# OBC_EEPROM.net
KiCad netlist of a schematic drawn in Altium Designer
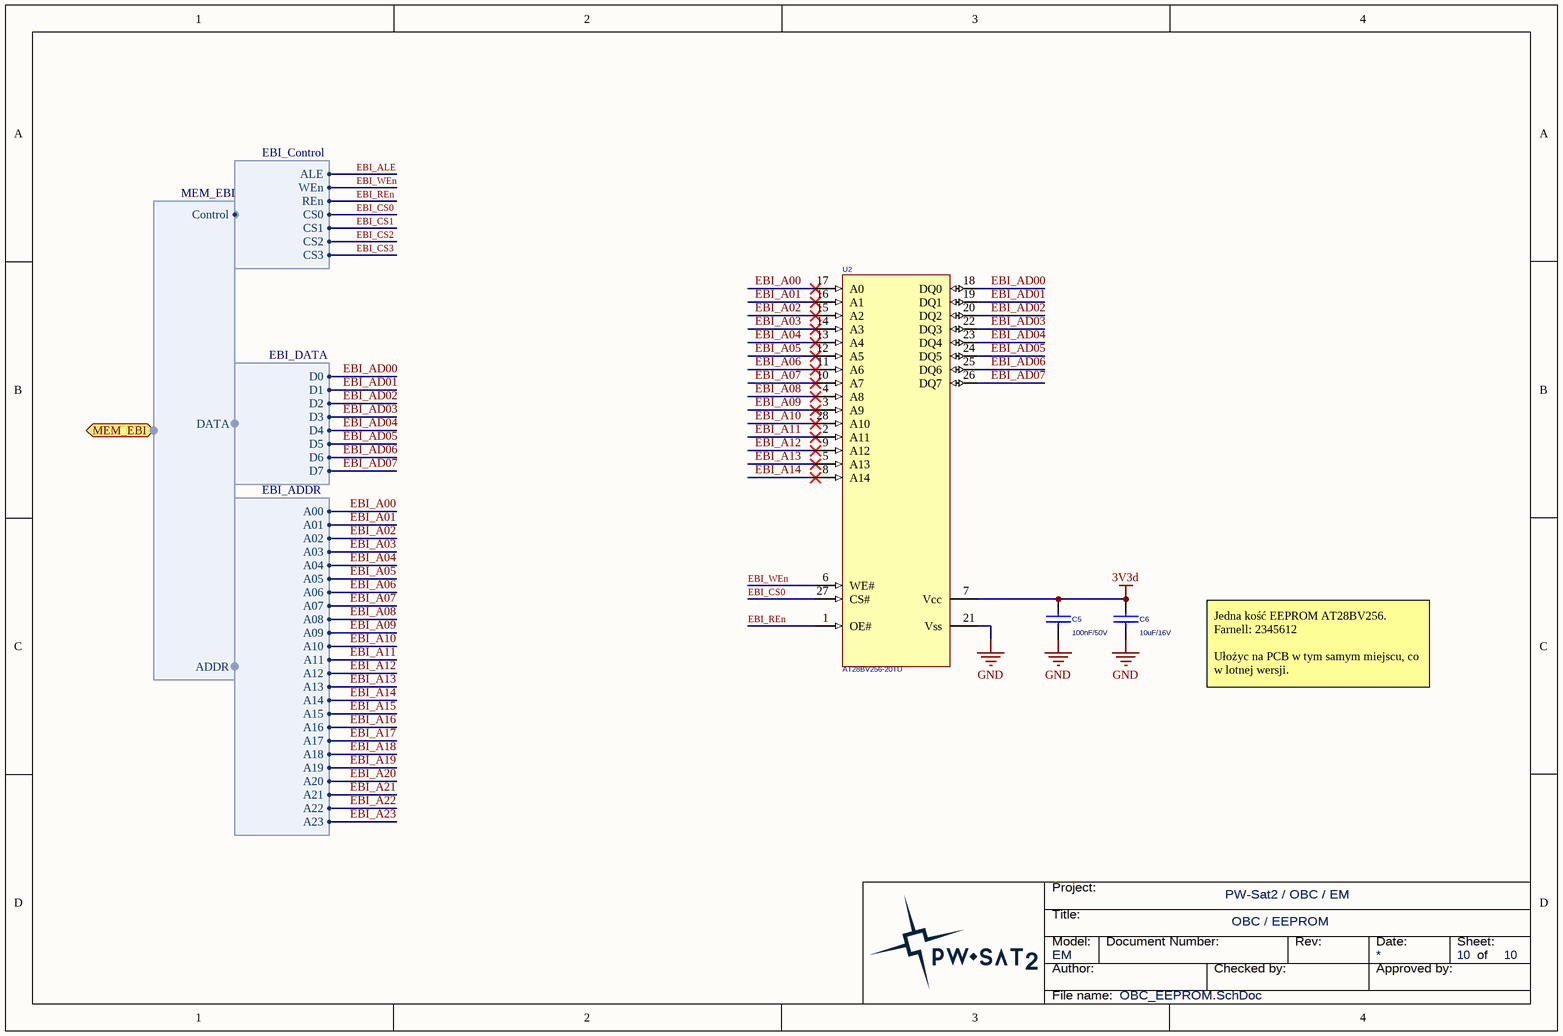
[diagram p0: OBC_EEPROM.SchDoc]

(export (version "E")
  (design (tool "Eeschema 10.0.6"))
  (components
    (comp (ref "C5")
      (value "100nF/50V")
      (footprint "C0603")
      (description "Capacitator")
      (fields (field (name "VOLTAGE") "50V"))
      (libsource (lib "SchLib") (part "CAP"))
    )
    (comp (ref "C6")
      (value "10uF/16V")
      (footprint "C1206")
      (description "Capacitator")
      (fields (field (name "VOLTAGE") "16V"))
      (libsource (lib "SchLib") (part "CAP"))
    )
    (comp (ref "U2")
      (value "AT28BV256-20TU")
      (footprint "TSOP-28T")
      (description "256K (32K x 8)  Battery-Voltage  Parallel  EEPROMs")
      (fields (field (name "MANUFACTURER") "Microchip Technology"))
      (libsource (lib "OBC") (part "AT28BV256-20TU"))
    )
  )
  (nets
    (net (code "2") (name "/EBI_A00") (class "Default")
      (node (ref "U2") (pin "17") (pinfunction "A0_17") (pintype "input"))
    )
    (net (code "3") (name "/EBI_A01") (class "Default")
      (node (ref "U2") (pin "16") (pinfunction "A1_16") (pintype "input"))
    )
    (net (code "4") (name "/EBI_A02") (class "Default")
      (node (ref "U2") (pin "15") (pinfunction "A2_15") (pintype "input"))
    )
    (net (code "5") (name "/EBI_A03") (class "Default")
      (node (ref "U2") (pin "14") (pinfunction "A3_14") (pintype "input"))
    )
    (net (code "6") (name "/EBI_A04") (class "Default")
      (node (ref "U2") (pin "13") (pinfunction "A4_13") (pintype "input"))
    )
    (net (code "7") (name "/EBI_A05") (class "Default")
      (node (ref "U2") (pin "12") (pinfunction "A5_12") (pintype "input+no_connect"))
    )
    (net (code "8") (name "/EBI_A06") (class "Default")
      (node (ref "U2") (pin "11") (pinfunction "A6_11") (pintype "input+no_connect"))
    )
    (net (code "9") (name "/EBI_A07") (class "Default")
      (node (ref "U2") (pin "10") (pinfunction "A7_10") (pintype "input+no_connect"))
    )
    (net (code "10") (name "/EBI_A08") (class "Default")
      (node (ref "U2") (pin "4") (pinfunction "A8_4") (pintype "input+no_connect"))
    )
    (net (code "11") (name "/EBI_A09") (class "Default")
      (node (ref "U2") (pin "3") (pinfunction "A9_3") (pintype "input+no_connect"))
    )
    (net (code "12") (name "/EBI_A10") (class "Default")
      (node (ref "U2") (pin "28") (pinfunction "A10_28") (pintype "input+no_connect"))
    )
    (net (code "13") (name "/EBI_A11") (class "Default")
      (node (ref "U2") (pin "2") (pinfunction "A11_2") (pintype "input+no_connect"))
    )
    (net (code "14") (name "/EBI_A12") (class "Default")
      (node (ref "U2") (pin "9") (pinfunction "A12_9") (pintype "input+no_connect"))
    )
    (net (code "15") (name "/EBI_A13") (class "Default")
      (node (ref "U2") (pin "5") (pinfunction "A13_5") (pintype "input+no_connect"))
    )
    (net (code "16") (name "/EBI_A14") (class "Default")
      (node (ref "U2") (pin "8") (pinfunction "A14_8") (pintype "input+no_connect"))
    )
    (net (code "26") (name "/EBI_AD00") (class "Default")
      (node (ref "U2") (pin "18") (pinfunction "DQ0_18") (pintype "bidirectional"))
    )
    (net (code "27") (name "/EBI_AD01") (class "Default")
      (node (ref "U2") (pin "19") (pinfunction "DQ1_19") (pintype "bidirectional"))
    )
    (net (code "28") (name "/EBI_AD02") (class "Default")
      (node (ref "U2") (pin "20") (pinfunction "DQ2_20") (pintype "bidirectional"))
    )
    (net (code "29") (name "/EBI_AD03") (class "Default")
      (node (ref "U2") (pin "22") (pinfunction "DQ3_22") (pintype "bidirectional"))
    )
    (net (code "30") (name "/EBI_AD04") (class "Default")
      (node (ref "U2") (pin "23") (pinfunction "DQ4_23") (pintype "bidirectional"))
    )
    (net (code "31") (name "/EBI_AD05") (class "Default")
      (node (ref "U2") (pin "24") (pinfunction "DQ5_24") (pintype "bidirectional"))
    )
    (net (code "32") (name "/EBI_AD06") (class "Default")
      (node (ref "U2") (pin "25") (pinfunction "DQ6_25") (pintype "bidirectional"))
    )
    (net (code "33") (name "/EBI_AD07") (class "Default")
      (node (ref "U2") (pin "26") (pinfunction "DQ7_26") (pintype "bidirectional"))
    )
    (net (code "35") (name "/EBI_CS0") (class "Default")
      (node (ref "U2") (pin "27") (pinfunction "CS#_27") (pintype "input"))
    )
    (net (code "39") (name "/EBI_REn") (class "Default")
      (node (ref "U2") (pin "1") (pinfunction "OE#_1") (pintype "input"))
    )
    (net (code "40") (name "/EBI_WEn") (class "Default")
      (node (ref "U2") (pin "6") (pinfunction "WE#_6") (pintype "input"))
    )
    (net (code "42") (name "3V3d") (class "Default")
      (node (ref "C5") (pin "1") (pintype "passive"))
      (node (ref "C6") (pin "1") (pintype "passive"))
      (node (ref "U2") (pin "7") (pinfunction "Vcc_7") (pintype "passive"))
    )
    (net (code "43") (name "GND") (class "Default")
      (node (ref "C5") (pin "2") (pintype "passive"))
      (node (ref "C6") (pin "2") (pintype "passive"))
      (node (ref "U2") (pin "21") (pinfunction "Vss_21") (pintype "passive"))
    )
  )
)
